# CAN_QSPI.net
KiCad netlist of a schematic drawn in Altium Designer
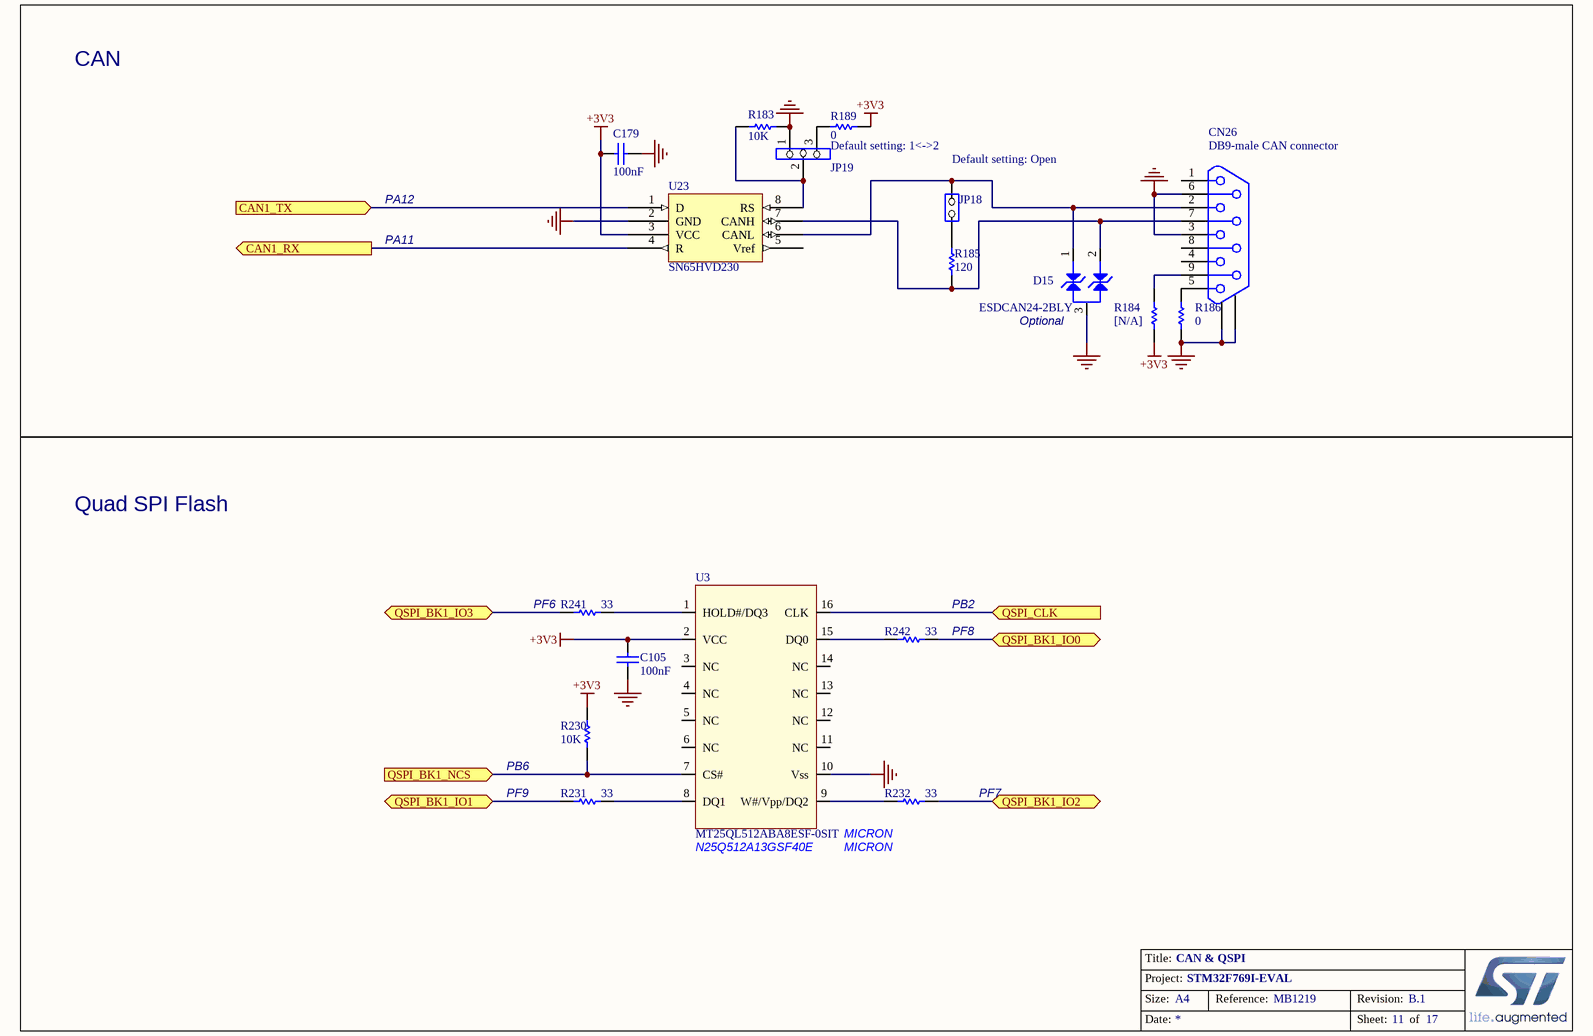
[diagram p0: CAN&QSPI.SchDoc]

(export (version "E")
  (design (tool "Eeschema 10.0.6"))
  (components
    (comp (ref "C105")
      (value "100nF")
      (footprint "0402C")
      (description "Capacitor")
      (fields (field (name "PUBLISHER") "Altium Limited"))
      (libsource (lib "Miscellaneous Devices") (part "Cap"))
    )
    (comp (ref "C179")
      (value "100nF")
      (footprint "0603C")
      (description "Capacitor")
      (fields (field (name "PUBLISHER") "Altium Limited"))
      (libsource (lib "Miscellaneous Devices") (part "Cap"))
    )
    (comp (ref "CN26")
      (value "DB9-male CAN connector")
      (footprint "DB9/M")
      (libsource (lib "MB1219") (part "DB9-CAN"))
    )
    (comp (ref "D15")
      (value "ESDCAN24-2BLY")
      (footprint "SOT-23")
      (libsource (lib "mb1045") (part "ESDCAN24-2BLY"))
    )
    (comp (ref "JP18") (value "~") (footprint "SIP2") (libsource (lib "*") (part "JP2")))
    (comp (ref "JP19") (value "~") (footprint "SIP3") (libsource (lib "STR910_SCHLIB") (part "Jumper3")))
    (comp (ref "R183")
      (value "10K")
      (footprint "0603R")
      (description "Resistor")
      (fields (field (name "PUBLISHER") "Altium Limited"))
      (libsource (lib "Miscellaneous Devices") (part "Res1"))
    )
    (comp (ref "R184")
      (value "[N/A]")
      (footprint "0603R")
      (description "Resistor")
      (fields (field (name "PUBLISHER") "Altium Limited"))
      (libsource (lib "Miscellaneous Devices") (part "res1"))
    )
    (comp (ref "R185")
      (value "120")
      (footprint "0603R")
      (description "Resistor")
      (fields (field (name "PUBLISHER") "Altium Limited"))
      (libsource (lib "Miscellaneous Devices") (part "res1"))
    )
    (comp (ref "R186")
      (value "0")
      (footprint "0603R")
      (description "Resistor")
      (fields (field (name "PUBLISHER") "Altium Limited"))
      (libsource (lib "Miscellaneous Devices") (part "res1"))
    )
    (comp (ref "R189")
      (value "0")
      (footprint "0603R")
      (description "Resistor")
      (fields (field (name "PUBLISHER") "Altium Limited"))
      (libsource (lib "Miscellaneous Devices") (part "res1"))
    )
    (comp (ref "R230")
      (value "10K")
      (footprint "0402R")
      (description "Resistor")
      (fields (field (name "PUBLISHER") "Altium Limited"))
      (libsource (lib "Miscellaneous Devices") (part "res1"))
    )
    (comp (ref "R231")
      (value "33")
      (footprint "0603R")
      (description "Resistor")
      (fields (field (name "PUBLISHER") "Altium Limited"))
      (libsource (lib "Miscellaneous Devices") (part "Res1"))
    )
    (comp (ref "R232")
      (value "33")
      (footprint "0603R")
      (description "Resistor")
      (fields (field (name "PUBLISHER") "Altium Limited"))
      (libsource (lib "Miscellaneous Devices") (part "Res1"))
    )
    (comp (ref "R241")
      (value "33")
      (footprint "0603R")
      (description "Resistor")
      (fields (field (name "PUBLISHER") "Altium Limited"))
      (libsource (lib "Miscellaneous Devices") (part "Res1"))
    )
    (comp (ref "R242")
      (value "33")
      (footprint "0603R")
      (description "Resistor")
      (fields (field (name "PUBLISHER") "Altium Limited"))
      (libsource (lib "Miscellaneous Devices") (part "Res1"))
    )
    (comp (ref "U3")
      (value "MT25QL512ABA8ESF-0SIT")
      (footprint "SOIC16W_1R27_10R3X10R33")
      (libsource (lib "MB1167") (part "QSPI_16pins"))
    )
    (comp (ref "U23")
      (value "SN65HVD230")
      (footprint "SOIC8_1R27_4R9X6")
      (libsource (lib "STR910_SCHLIB") (part "SN65HVD230D"))
    )
  )
  (nets
    (net (code "1") (name "+3V3") (class "Default")
      (node (ref "C105") (pin "1") (pinfunction "1_1") (pintype "passive"))
      (node (ref "C179") (pin "1") (pinfunction "1_1") (pintype "passive"))
      (node (ref "R184") (pin "1") (pinfunction "1_1") (pintype "passive"))
      (node (ref "R189") (pin "2") (pinfunction "2_2") (pintype "passive"))
      (node (ref "R230") (pin "1") (pinfunction "1_1") (pintype "passive"))
      (node (ref "U23") (pin "3") (pinfunction "VCC_3") (pintype "power_in"))
      (node (ref "U3") (pin "2") (pinfunction "VCC_2") (pintype "passive"))
    )
    (net (code "2") (name "/CAN1_RX") (class "Default")
      (node (ref "U23") (pin "4") (pinfunction "R_4") (pintype "output"))
    )
    (net (code "3") (name "/CAN1_TX") (class "Default")
      (node (ref "U23") (pin "1") (pinfunction "D_1") (pintype "input"))
    )
    (net (code "4") (name "/QSPI_BK1_IO0") (class "Default")
      (node (ref "R242") (pin "1") (pinfunction "1_1") (pintype "passive"))
    )
    (net (code "5") (name "/QSPI_BK1_IO1") (class "Default")
      (node (ref "R231") (pin "2") (pinfunction "2_2") (pintype "passive"))
    )
    (net (code "6") (name "/QSPI_BK1_IO2") (class "Default")
      (node (ref "R232") (pin "1") (pinfunction "1_1") (pintype "passive"))
    )
    (net (code "7") (name "/QSPI_BK1_IO3") (class "Default")
      (node (ref "R241") (pin "2") (pinfunction "2_2") (pintype "passive"))
    )
    (net (code "8") (name "/QSPI_BK1_NCS") (class "Default")
      (node (ref "R230") (pin "2") (pinfunction "2_2") (pintype "passive"))
      (node (ref "U3") (pin "7") (pinfunction "CS#_7") (pintype "passive"))
    )
    (net (code "9") (name "/QSPI_CLK") (class "Default")
      (node (ref "U3") (pin "16") (pinfunction "CLK_16") (pintype "passive"))
    )
    (net (code "10") (name "GND") (class "Default")
      (node (ref "C105") (pin "2") (pinfunction "2_2") (pintype "passive"))
      (node (ref "C179") (pin "2") (pinfunction "2_2") (pintype "passive"))
      (node (ref "CN26") (pin "10") (pinfunction "10_10") (pintype "passive"))
      (node (ref "CN26") (pin "11") (pinfunction "11_11") (pintype "passive"))
      (node (ref "CN26") (pin "3") (pinfunction "3_3") (pintype "passive"))
      (node (ref "CN26") (pin "6") (pinfunction "6_6") (pintype "passive"))
      (node (ref "D15") (pin "3") (pinfunction "3_3") (pintype "passive"))
      (node (ref "JP19") (pin "1") (pintype "passive"))
      (node (ref "R183") (pin "2") (pinfunction "2_2") (pintype "passive"))
      (node (ref "R186") (pin "1") (pinfunction "1_1") (pintype "passive"))
      (node (ref "U23") (pin "2") (pinfunction "GND_2") (pintype "power_in"))
      (node (ref "U3") (pin "10") (pinfunction "Vss_10") (pintype "passive"))
    )
    (net (code "11") (name "Net-(CN26-Pad5)") (class "Default")
      (node (ref "CN26") (pin "5") (pinfunction "5_5") (pintype "passive"))
      (node (ref "R186") (pin "2") (pinfunction "2_2") (pintype "passive"))
    )
    (net (code "12") (name "Net-(CN26-Pad9)") (class "Default")
      (node (ref "CN26") (pin "9") (pinfunction "9_9") (pintype "passive"))
      (node (ref "R184") (pin "2") (pinfunction "2_2") (pintype "passive"))
    )
    (net (code "13") (name "Net-(JP18-COMMON)") (class "Default")
      (node (ref "JP18") (pin "1") (pinfunction "COMMON_1") (pintype "passive"))
      (node (ref "R185") (pin "2") (pinfunction "2_2") (pintype "passive"))
    )
    (net (code "14") (name "Net-(JP18-NO)") (class "Default")
      (node (ref "CN26") (pin "2") (pinfunction "2_2") (pintype "passive"))
      (node (ref "D15") (pin "1") (pinfunction "1_1") (pintype "passive"))
      (node (ref "JP18") (pin "2") (pinfunction "NO_2") (pintype "passive"))
      (node (ref "U23") (pin "6") (pinfunction "CANL_6") (pintype "bidirectional"))
    )
    (net (code "15") (name "Net-(JP19-Pad3)") (class "Default")
      (node (ref "JP19") (pin "3") (pintype "passive"))
      (node (ref "R189") (pin "1") (pinfunction "1_1") (pintype "passive"))
    )
    (net (code "16") (name "Net-(U3-DQ0)") (class "Default")
      (node (ref "R242") (pin "2") (pinfunction "2_2") (pintype "passive"))
      (node (ref "U3") (pin "15") (pinfunction "DQ0_15") (pintype "passive"))
    )
    (net (code "17") (name "Net-(U3-DQ1)") (class "Default")
      (node (ref "R231") (pin "1") (pinfunction "1_1") (pintype "passive"))
      (node (ref "U3") (pin "8") (pinfunction "DQ1_8") (pintype "passive"))
    )
    (net (code "18") (name "Net-(U3-HOLD#{slash}DQ3)") (class "Default")
      (node (ref "R241") (pin "1") (pinfunction "1_1") (pintype "passive"))
      (node (ref "U3") (pin "1") (pinfunction "HOLD#/DQ3_1") (pintype "passive"))
    )
    (net (code "19") (name "Net-(U3-W#{slash}Vpp{slash}DQ2)") (class "Default")
      (node (ref "R232") (pin "2") (pinfunction "2_2") (pintype "passive"))
      (node (ref "U3") (pin "9") (pinfunction "W#/Vpp/DQ2_9") (pintype "passive"))
    )
    (net (code "20") (name "Net-(U23-CANH)") (class "Default")
      (node (ref "CN26") (pin "7") (pinfunction "7_7") (pintype "passive"))
      (node (ref "D15") (pin "2") (pinfunction "2_2") (pintype "passive"))
      (node (ref "R185") (pin "1") (pinfunction "1_1") (pintype "passive"))
      (node (ref "U23") (pin "7") (pinfunction "CANH_7") (pintype "bidirectional"))
    )
    (net (code "21") (name "Net-(U23-RS)") (class "Default")
      (node (ref "JP19") (pin "2") (pintype "passive"))
      (node (ref "R183") (pin "1") (pinfunction "1_1") (pintype "passive"))
      (node (ref "U23") (pin "8") (pinfunction "RS_8") (pintype "input"))
    )
    (net (code "22") (name "unconnected-(CN26-Pad1)") (class "Default")
      (node (ref "CN26") (pin "1") (pinfunction "1_1") (pintype "passive"))
    )
    (net (code "23") (name "unconnected-(CN26-Pad4)") (class "Default")
      (node (ref "CN26") (pin "4") (pinfunction "4_4") (pintype "passive"))
    )
    (net (code "24") (name "unconnected-(CN26-Pad8)") (class "Default")
      (node (ref "CN26") (pin "8") (pinfunction "8_8") (pintype "passive"))
    )
    (net (code "25") (name "unconnected-(U3-NC-Pad3)") (class "Default")
      (node (ref "U3") (pin "3") (pinfunction "NC_3") (pintype "passive"))
    )
    (net (code "26") (name "unconnected-(U3-NC-Pad4)") (class "Default")
      (node (ref "U3") (pin "4") (pinfunction "NC_4") (pintype "passive"))
    )
    (net (code "27") (name "unconnected-(U3-NC-Pad5)") (class "Default")
      (node (ref "U3") (pin "5") (pinfunction "NC_5") (pintype "passive"))
    )
    (net (code "28") (name "unconnected-(U3-NC-Pad6)") (class "Default")
      (node (ref "U3") (pin "6") (pinfunction "NC_6") (pintype "passive"))
    )
    (net (code "29") (name "unconnected-(U3-NC-Pad11)") (class "Default")
      (node (ref "U3") (pin "11") (pinfunction "NC_11") (pintype "passive"))
    )
    (net (code "30") (name "unconnected-(U3-NC-Pad12)") (class "Default")
      (node (ref "U3") (pin "12") (pinfunction "NC_12") (pintype "passive"))
    )
    (net (code "31") (name "unconnected-(U3-NC-Pad13)") (class "Default")
      (node (ref "U3") (pin "13") (pinfunction "NC_13") (pintype "passive"))
    )
    (net (code "32") (name "unconnected-(U3-NC-Pad14)") (class "Default")
      (node (ref "U3") (pin "14") (pinfunction "NC_14") (pintype "passive"))
    )
    (net (code "33") (name "unconnected-(U23-Vref-Pad5)") (class "Default")
      (node (ref "U23") (pin "5") (pinfunction "Vref_5") (pintype "output"))
    )
  )
)
